# main.net
KiCad netlist of a schematic drawn in Altium Designer
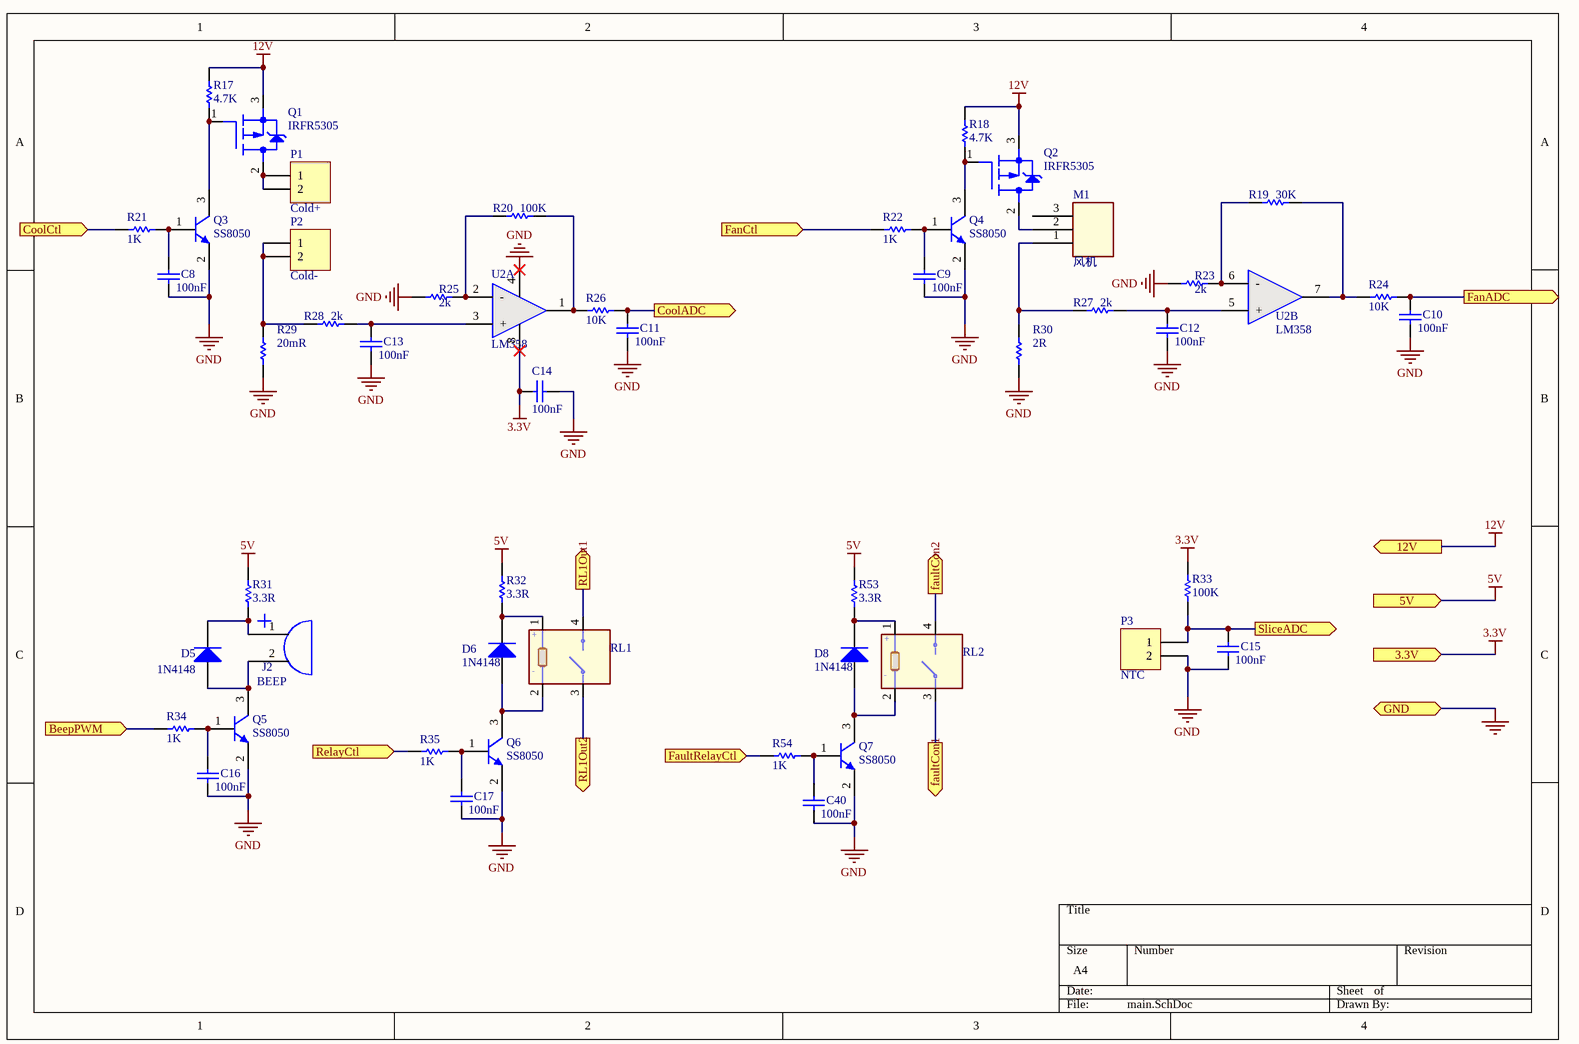
[diagram p0: main.SchDoc]

(export (version "E")
  (design (tool "Eeschema 10.0.6"))
  (components
    (comp (ref "C8")
      (value "100nF (104) 10% 50V")
      (footprint "0603_C")
      (description "贴片电容")
      (fields (field (name "ALTIUM_UNNAMED_1") "100nF"))
      (libsource (lib "Miscellaneous Devices LC") (part "0603 100nF (104) 10% 50V"))
    )
    (comp (ref "C9")
      (value "100nF (104) 10% 50V")
      (footprint "0603_C")
      (description "贴片电容")
      (fields (field (name "ALTIUM_UNNAMED_1") "100nF"))
      (libsource (lib "Miscellaneous Devices LC") (part "0603 100nF (104) 10% 50V"))
    )
    (comp (ref "C10")
      (value "100nF (104) 10% 50V")
      (footprint "0603_C")
      (description "贴片电容")
      (fields (field (name "ALTIUM_UNNAMED_1") "100nF"))
      (libsource (lib "Miscellaneous Devices LC") (part "0603 100nF (104) 10% 50V"))
    )
    (comp (ref "C11")
      (value "100nF (104) 10% 50V")
      (footprint "0603_C")
      (description "贴片电容")
      (fields (field (name "ALTIUM_UNNAMED_1") "100nF"))
      (libsource (lib "Miscellaneous Devices LC") (part "0603 100nF (104) 10% 50V"))
    )
    (comp (ref "C12")
      (value "100nF (104) 10% 50V")
      (footprint "0603_C")
      (description "贴片电容")
      (fields (field (name "ALTIUM_UNNAMED_1") "100nF"))
      (libsource (lib "Miscellaneous Devices LC") (part "0603 100nF (104) 10% 50V"))
    )
    (comp (ref "C13")
      (value "100nF (104) 10% 50V")
      (footprint "0603_C")
      (description "贴片电容")
      (fields (field (name "ALTIUM_UNNAMED_1") "100nF"))
      (libsource (lib "Miscellaneous Devices LC") (part "0603 100nF (104) 10% 50V"))
    )
    (comp (ref "C14")
      (value "100nF (104) 10% 50V")
      (footprint "0603_C")
      (description "贴片电容")
      (fields (field (name "ALTIUM_UNNAMED_1") "100nF"))
      (libsource (lib "Miscellaneous Devices LC") (part "0603 100nF (104) 10% 50V"))
    )
    (comp (ref "C15")
      (value "100nF (104) 10% 50V")
      (footprint "0603_C")
      (description "贴片电容")
      (fields (field (name "ALTIUM_UNNAMED_1") "100nF"))
      (libsource (lib "Miscellaneous Devices LC") (part "0603 100nF (104) 10% 50V"))
    )
    (comp (ref "C16")
      (value "100nF (104) 10% 50V")
      (footprint "0603_C")
      (description "贴片电容")
      (fields (field (name "ALTIUM_UNNAMED_1") "100nF"))
      (libsource (lib "Miscellaneous Devices LC") (part "0603 100nF (104) 10% 50V"))
    )
    (comp (ref "C17")
      (value "100nF (104) 10% 50V")
      (footprint "0603_C")
      (description "贴片电容")
      (fields (field (name "ALTIUM_UNNAMED_1") "100nF"))
      (libsource (lib "Miscellaneous Devices LC") (part "0603 100nF (104) 10% 50V"))
    )
    (comp (ref "C40")
      (value "100nF (104) 10% 50V")
      (footprint "0603_C")
      (description "贴片电容")
      (fields (field (name "ALTIUM_UNNAMED_1") "100nF"))
      (libsource (lib "Miscellaneous Devices LC") (part "0603 100nF (104) 10% 50V"))
    )
    (comp (ref "D5")
      (value "1N4148")
      (footprint "DIODE-1206")
      (description "二极管")
      (fields (field (name "PUBLISHER") "Altium Limited"))
      (libsource (lib "Fszhang") (part "Diode"))
    )
    (comp (ref "D6")
      (value "1N4148")
      (footprint "DIODE-1206")
      (description "二极管")
      (fields (field (name "PUBLISHER") "Altium Limited"))
      (libsource (lib "Fszhang") (part "Diode"))
    )
    (comp (ref "D8")
      (value "1N4148")
      (footprint "DIODE-1206")
      (description "二极管")
      (fields (field (name "PUBLISHER") "Altium Limited"))
      (libsource (lib "Fszhang") (part "Diode"))
    )
    (comp (ref "J2")
      (value "BEEP")
      (footprint "Beep0905")
      (description "蜂鸣器")
      (libsource (lib "fszhang") (part "BEEP"))
    )
    (comp (ref "M1")
      (value "风机")
      (footprint "connector3x2.5")
      (description "MALE CONN. 3 POLES P=7.62mm")
      (fields (field (name "APPROVED") "LANZONI L."))
      (libsource (lib "PCB_Project") (part "SACE_CON_3"))
    )
    (comp (ref "P1")
      (value "Cold+")
      (footprint "ConSlice0.5")
      (description "Header, 2-Pin")
      (fields (field (name "PUBLISHER") "Altium Limited"))
      (libsource (lib "") (part "Header 2_1"))
    )
    (comp (ref "P2")
      (value "Cold-")
      (footprint "ConSlice0.5")
      (description "Header, 2-Pin")
      (fields (field (name "PUBLISHER") "Altium Limited"))
      (libsource (lib "") (part "Header 2_1"))
    )
    (comp (ref "P3")
      (value "NTC")
      (footprint "HDR1X2_2")
      (description "Header, 2-Pin")
      (fields (field (name "PUBLISHER") "Altium Limited"))
      (libsource (lib "Miscellaneous Connectors") (part "Header 2"))
    )
    (comp (ref "Q1")
      (value "IRFR5305")
      (footprint "DPAK")
      (description "P-CH MOSFET LOGIC LEVEL 12A 60V SMD")
      (fields (field (name "VALORE") "IRFR5305") (field (name "APPROVED") "MANZOLI R."))
      (libsource (lib "PCB_Project") (part "SACE_MOSFET_P"))
    )
    (comp (ref "Q2")
      (value "IRFR5305")
      (footprint "DPAK")
      (description "P-CH MOSFET LOGIC LEVEL 12A 60V SMD")
      (fields (field (name "VALORE") "IRFR5305") (field (name "APPROVED") "MANZOLI R."))
      (libsource (lib "PCB_Project") (part "SACE_MOSFET_P"))
    )
    (comp (ref "Q3")
      (value "SS8050")
      (footprint "SOT-23")
      (description "NPN贴片三极管")
      (fields (field (name "PUBLISHER") "Altium Limited"))
      (libsource (lib "fszhang") (part "SS8050"))
    )
    (comp (ref "Q4")
      (value "SS8050")
      (footprint "SOT-23")
      (description "NPN贴片三极管")
      (fields (field (name "PUBLISHER") "Altium Limited"))
      (libsource (lib "fszhang") (part "SS8050"))
    )
    (comp (ref "Q5")
      (value "SS8050")
      (footprint "SOT-23")
      (description "NPN贴片三极管")
      (fields (field (name "PUBLISHER") "Altium Limited"))
      (libsource (lib "fszhang") (part "SS8050"))
    )
    (comp (ref "Q6")
      (value "SS8050")
      (footprint "SOT-23")
      (description "NPN贴片三极管")
      (fields (field (name "PUBLISHER") "Altium Limited"))
      (libsource (lib "fszhang") (part "SS8050"))
    )
    (comp (ref "Q7")
      (value "SS8050")
      (footprint "SOT-23")
      (description "NPN贴片三极管")
      (fields (field (name "PUBLISHER") "Altium Limited"))
      (libsource (lib "fszhang") (part "SS8050"))
    )
    (comp (ref "R17")
      (value "4.7K")
      (footprint "RESC1608N-R0603")
      (description "4.7K/±10%")
      (libsource (lib "Free Documents") (part "RES1"))
    )
    (comp (ref "R18")
      (value "4.7K")
      (footprint "RESC1608N-R0603")
      (description "4.7K/±10%")
      (libsource (lib "Free Documents") (part "RES1"))
    )
    (comp (ref "R19")
      (value "30K")
      (footprint "RESC1608N-R0603")
      (description "30K/±1%")
      (libsource (lib "Free Documents") (part "RES1"))
    )
    (comp (ref "R20")
      (value "100K")
      (footprint "RESC1608N-R0603")
      (description "100K/±10%")
      (libsource (lib "Free Documents") (part "RES1"))
    )
    (comp (ref "R21")
      (value "1K")
      (footprint "RESC1608N-R0603")
      (description "1K/±10%")
      (libsource (lib "Free Documents") (part "RES1"))
    )
    (comp (ref "R22")
      (value "1K")
      (footprint "RESC1608N-R0603")
      (description "1K/±10%")
      (libsource (lib "Free Documents") (part "RES1"))
    )
    (comp (ref "R23")
      (value "2k")
      (footprint "RESC1608N-R0603")
      (description "2k/±10%")
      (libsource (lib "Free Documents") (part "RES1"))
    )
    (comp (ref "R24")
      (value "10K")
      (footprint "RESC1608N-R0603")
      (description "10K/±10%")
      (libsource (lib "Free Documents") (part "RES1"))
    )
    (comp (ref "R25")
      (value "2k")
      (footprint "RESC1608N-R0603")
      (description "2k/±10%")
      (libsource (lib "Free Documents") (part "RES1"))
    )
    (comp (ref "R26")
      (value "10K")
      (footprint "RESC1608N-R0603")
      (description "10K/±10%")
      (libsource (lib "Free Documents") (part "RES1"))
    )
    (comp (ref "R27")
      (value "2k")
      (footprint "RESC1608N-R0603")
      (description "2k/±10%")
      (libsource (lib "Free Documents") (part "RES1"))
    )
    (comp (ref "R28")
      (value "2k")
      (footprint "RESC1608N-R0603")
      (description "2k/±10%")
      (libsource (lib "Free Documents") (part "RES1"))
    )
    (comp (ref "R29")
      (value "20mR")
      (footprint "Rsense10mm")
      (description "Resistor")
      (fields (field (name "PUBLISHER") "Altium Limited"))
      (libsource (lib "Miscellaneous Devices") (part "Res1"))
    )
    (comp (ref "R30")
      (value "2R")
      (footprint "R0.4x14.5")
      (description "Resistor")
      (fields (field (name "PUBLISHER") "Altium Limited"))
      (libsource (lib "Miscellaneous Devices") (part "Res1"))
    )
    (comp (ref "R31")
      (value "3.3R")
      (footprint "RESC1608N-R0603")
      (description "3.3R/±10%")
      (libsource (lib "Free Documents") (part "RES1"))
    )
    (comp (ref "R32")
      (value "3.3R")
      (footprint "RESC1608N-R0603")
      (description "3.3R/±10%")
      (libsource (lib "Free Documents") (part "RES1"))
    )
    (comp (ref "R33")
      (value "100K")
      (footprint "RESC1608N-R0603")
      (description "100K/±10%")
      (libsource (lib "Free Documents") (part "RES1"))
    )
    (comp (ref "R34")
      (value "1K")
      (footprint "RESC1608N-R0603")
      (description "1K/±10%")
      (libsource (lib "Free Documents") (part "RES1"))
    )
    (comp (ref "R35")
      (value "1K")
      (footprint "RESC1608N-R0603")
      (description "1K/±10%")
      (libsource (lib "Free Documents") (part "RES1"))
    )
    (comp (ref "R53")
      (value "3.3R")
      (footprint "RESC1608N-R0603")
      (description "3.3R/±10%")
      (libsource (lib "Free Documents") (part "RES1"))
    )
    (comp (ref "R54")
      (value "1K")
      (footprint "RESC1608N-R0603")
      (description "1K/±10%")
      (libsource (lib "Free Documents") (part "RES1"))
    )
    (comp (ref "RL1")
      (value "TXS2-24V")
      (footprint "ALDP112")
      (description "MONOSTABLE RELAY 2POLES 110V 1A COIL24V")
      (fields (field (name "APPROVED") "LANZONI L."))
      (libsource (lib "PCB_Project") (part "SACE_TXS2-24V_1"))
    )
    (comp (ref "RL2")
      (value "TXS2-24V")
      (footprint "ALDP112")
      (description "MONOSTABLE RELAY 2POLES 110V 1A COIL24V")
      (fields (field (name "APPROVED") "LANZONI L."))
      (libsource (lib "PCB_Project") (part "SACE_TXS2-24V_1"))
    )
    (comp (ref "U2")
      (value "LM358")
      (footprint "NSO8_N")
      (description "双运放")
      (libsource (lib "fszhang") (part "LM358"))
    )
  )
  (nets
    (net (code "1") (name "/BeepPWM") (class "Default")
      (node (ref "R34") (pin "2") (pinfunction "2_2") (pintype "passive"))
    )
    (net (code "2") (name "/CoolADC") (class "Default")
      (node (ref "C11") (pin "2") (pinfunction "2_2") (pintype "passive"))
      (node (ref "R26") (pin "1") (pinfunction "1_1") (pintype "passive"))
    )
    (net (code "3") (name "/CoolCtl") (class "Default")
      (node (ref "R21") (pin "2") (pinfunction "2_2") (pintype "passive"))
    )
    (net (code "4") (name "/FanADC") (class "Default")
      (node (ref "C10") (pin "2") (pinfunction "2_2") (pintype "passive"))
      (node (ref "R24") (pin "1") (pinfunction "1_1") (pintype "passive"))
    )
    (net (code "5") (name "/FanCtl") (class "Default")
      (node (ref "R22") (pin "2") (pinfunction "2_2") (pintype "passive"))
    )
    (net (code "6") (name "/FaultRelayCtl") (class "Default")
      (node (ref "R54") (pin "2") (pinfunction "2_2") (pintype "passive"))
    )
    (net (code "7") (name "/RL1Out1") (class "Default")
      (node (ref "RL1") (pin "4") (pinfunction "4_4") (pintype "passive"))
    )
    (net (code "8") (name "/RL1Out2") (class "Default")
      (node (ref "RL1") (pin "3") (pinfunction "3_3") (pintype "passive"))
    )
    (net (code "9") (name "/RelayCtl") (class "Default")
      (node (ref "R35") (pin "2") (pinfunction "2_2") (pintype "passive"))
    )
    (net (code "10") (name "/SliceADC") (class "Default")
      (node (ref "C15") (pin "2") (pinfunction "2_2") (pintype "passive"))
      (node (ref "P3") (pin "1") (pinfunction "1_1") (pintype "passive"))
      (node (ref "R33") (pin "2") (pinfunction "2_2") (pintype "passive"))
    )
    (net (code "11") (name "/faultCon1") (class "Default")
      (node (ref "RL2") (pin "3") (pinfunction "3_3") (pintype "passive"))
    )
    (net (code "12") (name "/faultCon2") (class "Default")
      (node (ref "RL2") (pin "4") (pinfunction "4_4") (pintype "passive"))
    )
    (net (code "13") (name "3.3V") (class "Default")
      (node (ref "C14") (pin "2") (pinfunction "2_2") (pintype "passive"))
      (node (ref "R33") (pin "1") (pinfunction "1_1") (pintype "passive"))
      (node (ref "U2") (pin "8") (pinfunction "V+_8") (pintype "power_in"))
    )
    (net (code "14") (name "5V") (class "Default")
      (node (ref "R31") (pin "1") (pinfunction "1_1") (pintype "passive"))
      (node (ref "R32") (pin "1") (pinfunction "1_1") (pintype "passive"))
      (node (ref "R53") (pin "1") (pinfunction "1_1") (pintype "passive"))
    )
    (net (code "15") (name "12V") (class "Default")
      (node (ref "Q1") (pin "3") (pinfunction "S_3") (pintype "passive"))
      (node (ref "Q2") (pin "3") (pinfunction "S_3") (pintype "passive"))
      (node (ref "R17") (pin "1") (pinfunction "1_1") (pintype "passive"))
      (node (ref "R18") (pin "1") (pinfunction "1_1") (pintype "passive"))
    )
    (net (code "16") (name "GND") (class "Default")
      (node (ref "C10") (pin "1") (pinfunction "1_1") (pintype "passive"))
      (node (ref "C11") (pin "1") (pinfunction "1_1") (pintype "passive"))
      (node (ref "C12") (pin "1") (pinfunction "1_1") (pintype "passive"))
      (node (ref "C13") (pin "1") (pinfunction "1_1") (pintype "passive"))
      (node (ref "C14") (pin "1") (pinfunction "1_1") (pintype "passive"))
      (node (ref "C15") (pin "1") (pinfunction "1_1") (pintype "passive"))
      (node (ref "C16") (pin "1") (pinfunction "1_1") (pintype "passive"))
      (node (ref "C17") (pin "1") (pinfunction "1_1") (pintype "passive"))
      (node (ref "C40") (pin "1") (pinfunction "1_1") (pintype "passive"))
      (node (ref "C8") (pin "1") (pinfunction "1_1") (pintype "passive"))
      (node (ref "C9") (pin "1") (pinfunction "1_1") (pintype "passive"))
      (node (ref "P3") (pin "2") (pinfunction "2_2") (pintype "passive"))
      (node (ref "Q3") (pin "2") (pinfunction "E_2") (pintype "passive"))
      (node (ref "Q4") (pin "2") (pinfunction "E_2") (pintype "passive"))
      (node (ref "Q5") (pin "2") (pinfunction "E_2") (pintype "passive"))
      (node (ref "Q6") (pin "2") (pinfunction "E_2") (pintype "passive"))
      (node (ref "Q7") (pin "2") (pinfunction "E_2") (pintype "passive"))
      (node (ref "R23") (pin "2") (pinfunction "2_2") (pintype "passive"))
      (node (ref "R25") (pin "2") (pinfunction "2_2") (pintype "passive"))
      (node (ref "R29") (pin "1") (pinfunction "1_1") (pintype "passive"))
      (node (ref "R30") (pin "1") (pinfunction "1_1") (pintype "passive"))
      (node (ref "U2") (pin "4") (pinfunction "V-_4") (pintype "power_in"))
    )
    (net (code "17") (name "Net-(D5-A)") (class "Default")
      (node (ref "D5") (pin "1") (pinfunction "A_1") (pintype "passive"))
      (node (ref "J2") (pin "2") (pinfunction "1_2") (pintype "passive"))
      (node (ref "Q5") (pin "3") (pinfunction "C_3") (pintype "passive"))
    )
    (net (code "18") (name "Net-(D5-K)") (class "Default")
      (node (ref "D5") (pin "2") (pinfunction "K_2") (pintype "passive"))
      (node (ref "J2") (pin "1") (pinfunction "0_1") (pintype "passive"))
      (node (ref "R31") (pin "2") (pinfunction "2_2") (pintype "passive"))
    )
    (net (code "19") (name "Net-(D6-A)") (class "Default")
      (node (ref "D6") (pin "1") (pinfunction "A_1") (pintype "passive"))
      (node (ref "Q6") (pin "3") (pinfunction "C_3") (pintype "passive"))
      (node (ref "RL1") (pin "2") (pinfunction "2_2") (pintype "passive"))
    )
    (net (code "20") (name "Net-(D6-K)") (class "Default")
      (node (ref "D6") (pin "2") (pinfunction "K_2") (pintype "passive"))
      (node (ref "R32") (pin "2") (pinfunction "2_2") (pintype "passive"))
      (node (ref "RL1") (pin "1") (pinfunction "1_1") (pintype "passive"))
    )
    (net (code "21") (name "Net-(D8-A)") (class "Default")
      (node (ref "D8") (pin "1") (pinfunction "A_1") (pintype "passive"))
      (node (ref "Q7") (pin "3") (pinfunction "C_3") (pintype "passive"))
      (node (ref "RL2") (pin "2") (pinfunction "2_2") (pintype "passive"))
    )
    (net (code "22") (name "Net-(D8-K)") (class "Default")
      (node (ref "D8") (pin "2") (pinfunction "K_2") (pintype "passive"))
      (node (ref "R53") (pin "2") (pinfunction "2_2") (pintype "passive"))
      (node (ref "RL2") (pin "1") (pinfunction "1_1") (pintype "passive"))
    )
    (net (code "23") (name "Net-(M1-Pad1)") (class "Default")
      (node (ref "M1") (pin "1") (pinfunction "1_1") (pintype "passive"))
      (node (ref "R27") (pin "2") (pinfunction "2_2") (pintype "passive"))
      (node (ref "R30") (pin "2") (pinfunction "2_2") (pintype "passive"))
    )
    (net (code "24") (name "Net-(P2-Pad1)") (class "Default")
      (node (ref "P2") (pin "1") (pinfunction "1_1") (pintype "passive"))
      (node (ref "P2") (pin "2") (pinfunction "2_2") (pintype "passive"))
      (node (ref "R28") (pin "2") (pinfunction "2_2") (pintype "passive"))
      (node (ref "R29") (pin "2") (pinfunction "2_2") (pintype "passive"))
    )
    (net (code "25") (name "Net-(Q1-D)") (class "Default")
      (node (ref "P1") (pin "1") (pinfunction "1_1") (pintype "passive"))
      (node (ref "P1") (pin "2") (pinfunction "2_2") (pintype "passive"))
      (node (ref "Q1") (pin "2") (pinfunction "D_2") (pintype "passive"))
    )
    (net (code "26") (name "Net-(Q1-G)") (class "Default")
      (node (ref "Q1") (pin "1") (pinfunction "G_1") (pintype "passive"))
      (node (ref "Q3") (pin "3") (pinfunction "C_3") (pintype "passive"))
      (node (ref "R17") (pin "2") (pinfunction "2_2") (pintype "passive"))
    )
    (net (code "27") (name "Net-(Q2-D)") (class "Default")
      (node (ref "M1") (pin "2") (pinfunction "2_2") (pintype "passive"))
      (node (ref "Q2") (pin "2") (pinfunction "D_2") (pintype "passive"))
    )
    (net (code "28") (name "Net-(Q2-G)") (class "Default")
      (node (ref "Q2") (pin "1") (pinfunction "G_1") (pintype "passive"))
      (node (ref "Q4") (pin "3") (pinfunction "C_3") (pintype "passive"))
      (node (ref "R18") (pin "2") (pinfunction "2_2") (pintype "passive"))
    )
    (net (code "29") (name "Net-(Q3-B)") (class "Default")
      (node (ref "C8") (pin "2") (pinfunction "2_2") (pintype "passive"))
      (node (ref "Q3") (pin "1") (pinfunction "B_1") (pintype "passive"))
      (node (ref "R21") (pin "1") (pinfunction "1_1") (pintype "passive"))
    )
    (net (code "30") (name "Net-(Q4-B)") (class "Default")
      (node (ref "C9") (pin "2") (pinfunction "2_2") (pintype "passive"))
      (node (ref "Q4") (pin "1") (pinfunction "B_1") (pintype "passive"))
      (node (ref "R22") (pin "1") (pinfunction "1_1") (pintype "passive"))
    )
    (net (code "31") (name "Net-(Q5-B)") (class "Default")
      (node (ref "C16") (pin "2") (pinfunction "2_2") (pintype "passive"))
      (node (ref "Q5") (pin "1") (pinfunction "B_1") (pintype "passive"))
      (node (ref "R34") (pin "1") (pinfunction "1_1") (pintype "passive"))
    )
    (net (code "32") (name "Net-(Q6-B)") (class "Default")
      (node (ref "C17") (pin "2") (pinfunction "2_2") (pintype "passive"))
      (node (ref "Q6") (pin "1") (pinfunction "B_1") (pintype "passive"))
      (node (ref "R35") (pin "1") (pinfunction "1_1") (pintype "passive"))
    )
    (net (code "33") (name "Net-(Q7-B)") (class "Default")
      (node (ref "C40") (pin "2") (pinfunction "2_2") (pintype "passive"))
      (node (ref "Q7") (pin "1") (pinfunction "B_1") (pintype "passive"))
      (node (ref "R54") (pin "1") (pinfunction "1_1") (pintype "passive"))
    )
    (net (code "34") (name "Net-(U2A-+)") (class "Default")
      (node (ref "C13") (pin "2") (pinfunction "2_2") (pintype "passive"))
      (node (ref "R28") (pin "1") (pinfunction "1_1") (pintype "passive"))
      (node (ref "U2") (pin "3") (pinfunction "+_3") (pintype "passive"))
    )
    (net (code "35") (name "Net-(U2A--)") (class "Default")
      (node (ref "R20") (pin "2") (pinfunction "2_2") (pintype "passive"))
      (node (ref "R25") (pin "1") (pinfunction "1_1") (pintype "passive"))
      (node (ref "U2") (pin "2") (pinfunction "-_2") (pintype "passive"))
    )
    (net (code "36") (name "Net-(U2A-OUT1)") (class "Default")
      (node (ref "R20") (pin "1") (pinfunction "1_1") (pintype "passive"))
      (node (ref "R26") (pin "2") (pinfunction "2_2") (pintype "passive"))
      (node (ref "U2") (pin "1") (pinfunction "OUT1_1") (pintype "passive"))
    )
    (net (code "37") (name "Net-(U2B-+)") (class "Default")
      (node (ref "C12") (pin "2") (pinfunction "2_2") (pintype "passive"))
      (node (ref "R27") (pin "1") (pinfunction "1_1") (pintype "passive"))
      (node (ref "U2") (pin "5") (pinfunction "+_5") (pintype "passive"))
    )
    (net (code "38") (name "Net-(U2B--)") (class "Default")
      (node (ref "R19") (pin "2") (pinfunction "2_2") (pintype "passive"))
      (node (ref "R23") (pin "1") (pinfunction "1_1") (pintype "passive"))
      (node (ref "U2") (pin "6") (pinfunction "-_6") (pintype "passive"))
    )
    (net (code "39") (name "Net-(U2B-OUT2)") (class "Default")
      (node (ref "R19") (pin "1") (pinfunction "1_1") (pintype "passive"))
      (node (ref "R24") (pin "2") (pinfunction "2_2") (pintype "passive"))
      (node (ref "U2") (pin "7") (pinfunction "OUT2_7") (pintype "passive"))
    )
    (net (code "40") (name "unconnected-(M1-Pad3)") (class "Default")
      (node (ref "M1") (pin "3") (pinfunction "3_3") (pintype "passive"))
    )
  )
)
